# 6_ETHERCAT.net
KiCad netlist of a schematic drawn in Altium Designer
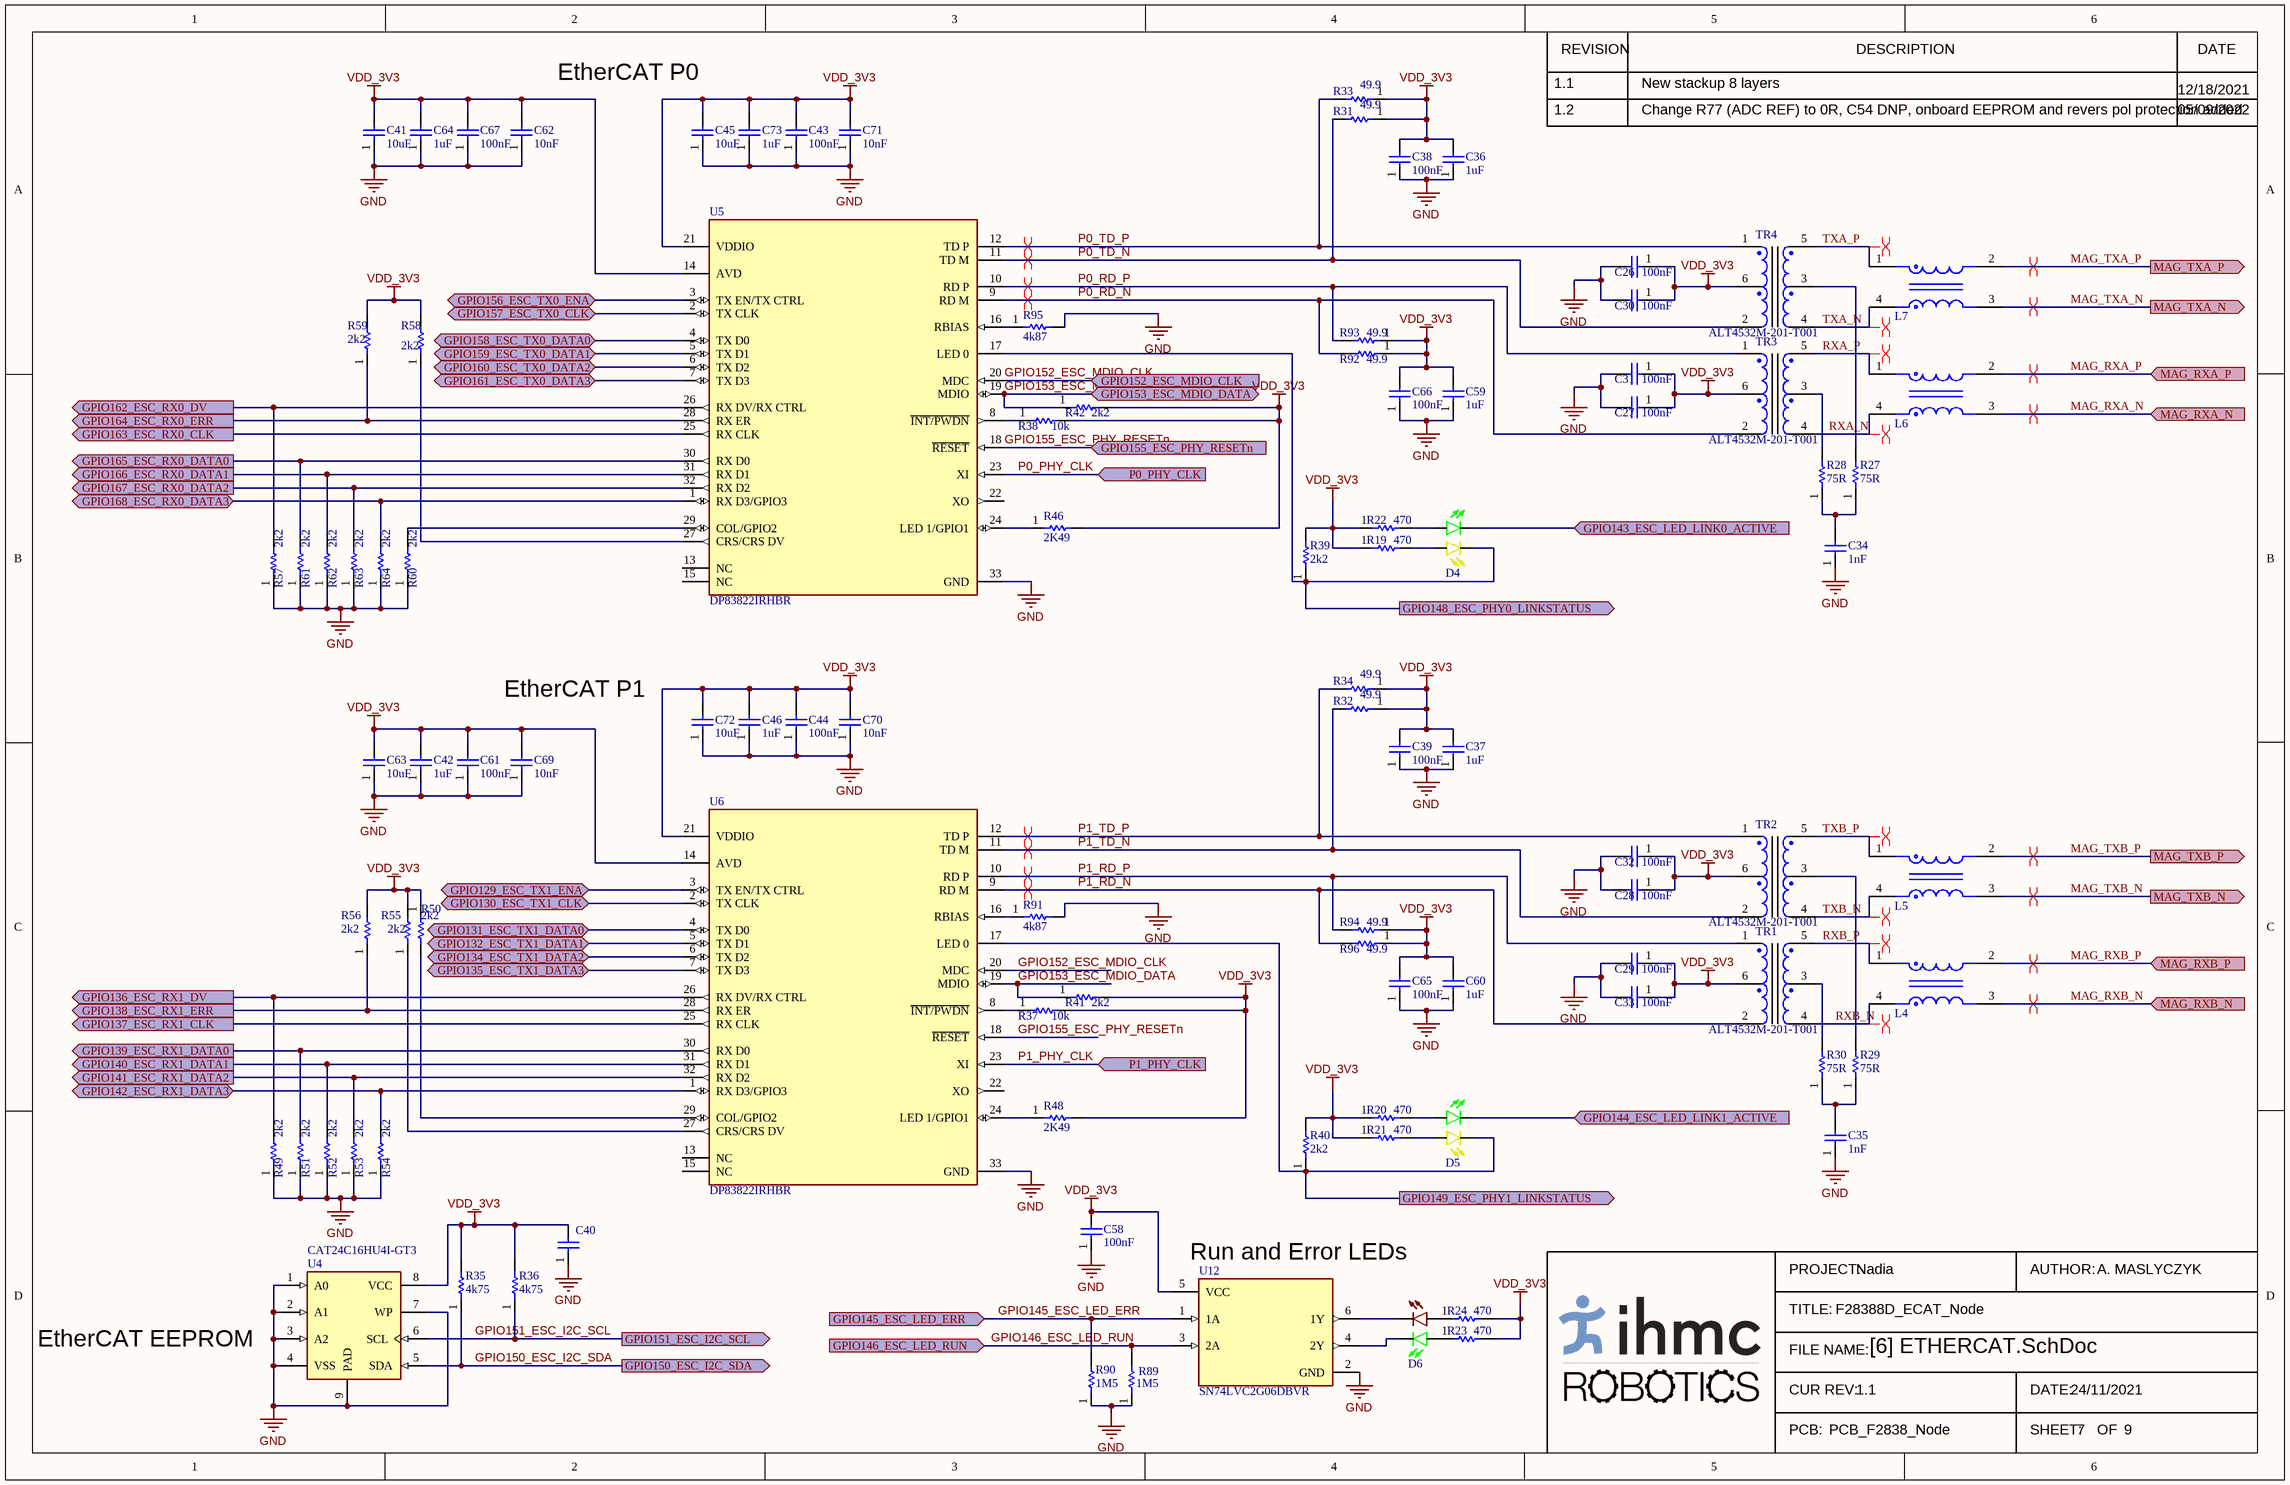
[diagram p0: [6] ETHERCAT.SchDoc]

(export (version "E")
  (design (tool "Eeschema 10.0.6"))
  (components
    (comp (ref "C26")
      (value "100nF")
      (footprint "CAPC1005X03N(0402)")
      (description "CAP CER 0.1UF 16V X7R 0402")
      (fields (field (name "MPN") "GRM155R71C104JA88D") (field (name "TOLERANCE") "5%"))
      (libsource (lib "IHMC_Altium_Lib") (part "100nF_16V_0402_CAP"))
    )
    (comp (ref "C27")
      (value "100nF")
      (footprint "CAPC1005X03N(0402)")
      (description "CAP CER 0.1UF 16V X7R 0402")
      (fields (field (name "MPN") "GRM155R71C104JA88D") (field (name "TOLERANCE") "5%"))
      (libsource (lib "IHMC_Altium_Lib") (part "100nF_16V_0402_CAP"))
    )
    (comp (ref "C28")
      (value "100nF")
      (footprint "CAPC1005X03N(0402)")
      (description "CAP CER 0.1UF 16V X7R 0402")
      (fields (field (name "MPN") "GRM155R71C104JA88D") (field (name "TOLERANCE") "5%"))
      (libsource (lib "IHMC_Altium_Lib") (part "100nF_16V_0402_CAP"))
    )
    (comp (ref "C29")
      (value "100nF")
      (footprint "CAPC1005X03N(0402)")
      (description "CAP CER 0.1UF 16V X7R 0402")
      (fields (field (name "MPN") "GRM155R71C104JA88D") (field (name "TOLERANCE") "5%"))
      (libsource (lib "IHMC_Altium_Lib") (part "100nF_16V_0402_CAP"))
    )
    (comp (ref "C30")
      (value "100nF")
      (footprint "CAPC1005X03N(0402)")
      (description "CAP CER 0.1UF 16V X7R 0402")
      (fields (field (name "MPN") "GRM155R71C104JA88D") (field (name "TOLERANCE") "5%"))
      (libsource (lib "IHMC_Altium_Lib") (part "100nF_16V_0402_CAP"))
    )
    (comp (ref "C31")
      (value "100nF")
      (footprint "CAPC1005X03N(0402)")
      (description "CAP CER 0.1UF 16V X7R 0402")
      (fields (field (name "MPN") "GRM155R71C104JA88D") (field (name "TOLERANCE") "5%"))
      (libsource (lib "IHMC_Altium_Lib") (part "100nF_16V_0402_CAP"))
    )
    (comp (ref "C32")
      (value "100nF")
      (footprint "CAPC1005X03N(0402)")
      (description "CAP CER 0.1UF 16V X7R 0402")
      (fields (field (name "MPN") "GRM155R71C104JA88D") (field (name "TOLERANCE") "5%"))
      (libsource (lib "IHMC_Altium_Lib") (part "100nF_16V_0402_CAP"))
    )
    (comp (ref "C33")
      (value "100nF")
      (footprint "CAPC1005X03N(0402)")
      (description "CAP CER 0.1UF 16V X7R 0402")
      (fields (field (name "MPN") "GRM155R71C104JA88D") (field (name "TOLERANCE") "5%"))
      (libsource (lib "IHMC_Altium_Lib") (part "100nF_16V_0402_CAP"))
    )
    (comp (ref "C34")
      (value "1nF")
      (footprint "0402_C")
      (description "CAP CER 1000PF 50V NP0 0402")
      (fields (field (name "TOLERANCE") "5%") (field (name "MANUFACTURER") "TDK"))
      (libsource (lib "IHMC_Altium_Lib") (part "1nF_50V_0402_C0G_CAP"))
    )
    (comp (ref "C35")
      (value "1nF")
      (footprint "0402_C")
      (description "CAP CER 1000PF 50V NP0 0402")
      (fields (field (name "TOLERANCE") "5%") (field (name "MANUFACTURER") "TDK"))
      (libsource (lib "IHMC_Altium_Lib") (part "1nF_50V_0402_C0G_CAP"))
    )
    (comp (ref "C36")
      (value "1uF")
      (footprint "CAPC1608X09N(0603)")
      (description "MLCC - SMD/SMT 25volts 1uF X5R 10%")
      (fields
        (field (name "MPN") "C0603C105K3PACTU")
        (field (name "VOLTAGE") "25VDC")
        (field (name "DRAWN BY") "TC")
      )
      (libsource (lib "IHMC_Altium_Lib") (part "1uF_25VDC_0603_Cap"))
    )
    (comp (ref "C37")
      (value "1uF")
      (footprint "CAPC1608X09N(0603)")
      (description "MLCC - SMD/SMT 25volts 1uF X5R 10%")
      (fields
        (field (name "MPN") "C0603C105K3PACTU")
        (field (name "VOLTAGE") "25VDC")
        (field (name "DRAWN BY") "TC")
      )
      (libsource (lib "IHMC_Altium_Lib") (part "1uF_25VDC_0603_Cap"))
    )
    (comp (ref "C38")
      (value "100nF")
      (footprint "CAPC1005X03N(0402)")
      (description "CAP CER 0.1UF 16V X7R 0402")
      (fields (field (name "MPN") "GRM155R71C104JA88D") (field (name "TOLERANCE") "5%"))
      (libsource (lib "IHMC_Altium_Lib") (part "100nF_16V_0402_CAP"))
    )
    (comp (ref "C39")
      (value "100nF")
      (footprint "CAPC1005X03N(0402)")
      (description "CAP CER 0.1UF 16V X7R 0402")
      (fields (field (name "MPN") "GRM155R71C104JA88D") (field (name "TOLERANCE") "5%"))
      (libsource (lib "IHMC_Altium_Lib") (part "100nF_16V_0402_CAP"))
    )
    (comp (ref "C40")
      (value "GRM155R71C104JA88D")
      (footprint "CAPC1005X03N(0402)")
      (description "CAP CER 0.1UF 16V X7R 0402")
      (fields (field (name "TOLERANCE") "5%"))
      (libsource (lib "IHMC_Altium_Lib") (part "100nF_16V_0402_CAP"))
    )
    (comp (ref "C41")
      (value "10uF")
      (footprint "CAPC1608X09N(0603)")
      (description "CAP CER 10UF 16V X6S 0603")
      (fields (field (name "MPN") "CL10X106MO8NRNC") (field (name "TOLERANCE") "20%"))
      (libsource (lib "IHMC_Altium_Lib") (part "10uF_16V_0603_CAP"))
    )
    (comp (ref "C42")
      (value "1uF")
      (footprint "CAPC1608X09N(0603)")
      (description "MLCC - SMD/SMT 25volts 1uF X5R 10%")
      (fields
        (field (name "MPN") "C0603C105K3PACTU")
        (field (name "VOLTAGE") "25VDC")
        (field (name "DRAWN BY") "TC")
      )
      (libsource (lib "IHMC_Altium_Lib") (part "1uF_25VDC_0603_Cap"))
    )
    (comp (ref "C43")
      (value "100nF")
      (footprint "CAPC1005X03N(0402)")
      (description "CAP CER 0.1UF 16V X7R 0402")
      (fields (field (name "MPN") "GRM155R71C104JA88D") (field (name "TOLERANCE") "5%"))
      (libsource (lib "IHMC_Altium_Lib") (part "100nF_16V_0402_CAP"))
    )
    (comp (ref "C44")
      (value "100nF")
      (footprint "CAPC1005X03N(0402)")
      (description "CAP CER 0.1UF 16V X7R 0402")
      (fields (field (name "MPN") "GRM155R71C104JA88D") (field (name "TOLERANCE") "5%"))
      (libsource (lib "IHMC_Altium_Lib") (part "100nF_16V_0402_CAP"))
    )
    (comp (ref "C45")
      (value "10uF")
      (footprint "CAPC1608X09N(0603)")
      (description "CAP CER 10UF 16V X6S 0603")
      (fields (field (name "MPN") "CL10X106MO8NRNC") (field (name "TOLERANCE") "20%"))
      (libsource (lib "IHMC_Altium_Lib") (part "10uF_16V_0603_CAP"))
    )
    (comp (ref "C46")
      (value "1uF")
      (footprint "CAPC1608X09N(0603)")
      (description "MLCC - SMD/SMT 25volts 1uF X5R 10%")
      (fields
        (field (name "MPN") "C0603C105K3PACTU")
        (field (name "VOLTAGE") "25VDC")
        (field (name "DRAWN BY") "TC")
      )
      (libsource (lib "IHMC_Altium_Lib") (part "1uF_25VDC_0603_Cap"))
    )
    (comp (ref "C58")
      (value "100nF")
      (footprint "CAPC1005X03N(0402)")
      (description "CAP CER 0.1UF 16V X7R 0402")
      (fields (field (name "MPN") "GRM155R71C104JA88D") (field (name "TOLERANCE") "5%"))
      (libsource (lib "IHMC_Altium_Lib") (part "100nF_16V_0402_CAP"))
    )
    (comp (ref "C59")
      (value "1uF")
      (footprint "CAPC1608X09N(0603)")
      (description "MLCC - SMD/SMT 25volts 1uF X5R 10%")
      (fields
        (field (name "MPN") "C0603C105K3PACTU")
        (field (name "VOLTAGE") "25VDC")
        (field (name "DRAWN BY") "TC")
      )
      (libsource (lib "IHMC_Altium_Lib") (part "1uF_25VDC_0603_Cap"))
    )
    (comp (ref "C60")
      (value "1uF")
      (footprint "CAPC1608X09N(0603)")
      (description "MLCC - SMD/SMT 25volts 1uF X5R 10%")
      (fields
        (field (name "MPN") "C0603C105K3PACTU")
        (field (name "VOLTAGE") "25VDC")
        (field (name "DRAWN BY") "TC")
      )
      (libsource (lib "IHMC_Altium_Lib") (part "1uF_25VDC_0603_Cap"))
    )
    (comp (ref "C61")
      (value "100nF")
      (footprint "CAPC1005X03N(0402)")
      (description "CAP CER 0.1UF 16V X7R 0402")
      (fields (field (name "MPN") "GRM155R71C104JA88D") (field (name "TOLERANCE") "5%"))
      (libsource (lib "IHMC_Altium_Lib") (part "100nF_16V_0402_CAP"))
    )
    (comp (ref "C62")
      (value "10nF")
      (footprint "CAPC1005X03N(0402)")
      (description "CAP CER 10000PF 50V X7R 0402")
      (fields (field (name "MPN") "CC0402KRX7R9BB103") (field (name "VOLTAGE") "50V"))
      (libsource (lib "IHMC_Altium_Lib") (part "10nF_50V_0402_CAP"))
    )
    (comp (ref "C63")
      (value "10uF")
      (footprint "CAPC1608X09N(0603)")
      (description "CAP CER 10UF 16V X6S 0603")
      (fields (field (name "MPN") "CL10X106MO8NRNC") (field (name "TOLERANCE") "20%"))
      (libsource (lib "IHMC_Altium_Lib") (part "10uF_16V_0603_CAP"))
    )
    (comp (ref "C64")
      (value "1uF")
      (footprint "CAPC1608X09N(0603)")
      (description "MLCC - SMD/SMT 25volts 1uF X5R 10%")
      (fields
        (field (name "MPN") "C0603C105K3PACTU")
        (field (name "VOLTAGE") "25VDC")
        (field (name "DRAWN BY") "TC")
      )
      (libsource (lib "IHMC_Altium_Lib") (part "1uF_25VDC_0603_Cap"))
    )
    (comp (ref "C65")
      (value "100nF")
      (footprint "CAPC1005X03N(0402)")
      (description "CAP CER 0.1UF 16V X7R 0402")
      (fields (field (name "MPN") "GRM155R71C104JA88D") (field (name "TOLERANCE") "5%"))
      (libsource (lib "IHMC_Altium_Lib") (part "100nF_16V_0402_CAP"))
    )
    (comp (ref "C66")
      (value "100nF")
      (footprint "CAPC1005X03N(0402)")
      (description "CAP CER 0.1UF 16V X7R 0402")
      (fields (field (name "MPN") "GRM155R71C104JA88D") (field (name "TOLERANCE") "5%"))
      (libsource (lib "IHMC_Altium_Lib") (part "100nF_16V_0402_CAP"))
    )
    (comp (ref "C67")
      (value "100nF")
      (footprint "CAPC1005X03N(0402)")
      (description "CAP CER 0.1UF 16V X7R 0402")
      (fields (field (name "MPN") "GRM155R71C104JA88D") (field (name "TOLERANCE") "5%"))
      (libsource (lib "IHMC_Altium_Lib") (part "100nF_16V_0402_CAP"))
    )
    (comp (ref "C69")
      (value "10nF")
      (footprint "CAPC1005X03N(0402)")
      (description "CAP CER 10000PF 50V X7R 0402")
      (fields (field (name "MPN") "CC0402KRX7R9BB103") (field (name "VOLTAGE") "50V"))
      (libsource (lib "IHMC_Altium_Lib") (part "10nF_50V_0402_CAP"))
    )
    (comp (ref "C70")
      (value "10nF")
      (footprint "CAPC1005X03N(0402)")
      (description "CAP CER 10000PF 50V X7R 0402")
      (fields (field (name "MPN") "CC0402KRX7R9BB103") (field (name "VOLTAGE") "50V"))
      (libsource (lib "IHMC_Altium_Lib") (part "10nF_50V_0402_CAP"))
    )
    (comp (ref "C71")
      (value "10nF")
      (footprint "CAPC1005X03N(0402)")
      (description "CAP CER 10000PF 50V X7R 0402")
      (fields (field (name "MPN") "CC0402KRX7R9BB103") (field (name "VOLTAGE") "50V"))
      (libsource (lib "IHMC_Altium_Lib") (part "10nF_50V_0402_CAP"))
    )
    (comp (ref "C72")
      (value "10uF")
      (footprint "CAPC1608X09N(0603)")
      (description "CAP CER 10UF 16V X6S 0603")
      (fields (field (name "MPN") "CL10X106MO8NRNC") (field (name "TOLERANCE") "20%"))
      (libsource (lib "IHMC_Altium_Lib") (part "10uF_16V_0603_CAP"))
    )
    (comp (ref "C73")
      (value "1uF")
      (footprint "CAPC1608X09N(0603)")
      (description "MLCC - SMD/SMT 25volts 1uF X5R 10%")
      (fields
        (field (name "MPN") "C0603C105K3PACTU")
        (field (name "VOLTAGE") "25VDC")
        (field (name "DRAWN BY") "TC")
      )
      (libsource (lib "IHMC_Altium_Lib") (part "1uF_25VDC_0603_Cap"))
    )
    (comp (ref "D4")
      (value "LTST-C195KGJSKT")
      (footprint "Dual_LED")
      (description "LED GREEN/YELLOW CLEAR CHIP SMD")
      (libsource (lib "IHMC_Altium_Lib") (part "Green/Yellow_LED"))
    )
    (comp (ref "D5")
      (value "LTST-C195KGJSKT")
      (footprint "Dual_LED")
      (description "LED GREEN/YELLOW CLEAR CHIP SMD")
      (libsource (lib "IHMC_Altium_Lib") (part "Green/Yellow_LED"))
    )
    (comp (ref "D6")
      (value "LTST-C195KGJRKT")
      (footprint "Dual_LED")
      (description "LED GREEN/RED CLEAR CHIP SMD")
      (libsource (lib "IHMC_Altium_Lib") (part "Green/Red_LED"))
    )
    (comp (ref "L4")
      (value "DLW21HN900SQ2L")
      (footprint "FP-DLW21HN-MFG")
      (fields (field (name "TOLERANCE") "25%") (field (name "MANUFACTURER") "Murata"))
      (libsource (lib "IHMC_Altium_Lib") (part "CM_CHOKE_90O_DLW21HN900SQ2L"))
    )
    (comp (ref "L5")
      (value "DLW21HN900SQ2L")
      (footprint "FP-DLW21HN-MFG")
      (fields (field (name "TOLERANCE") "25%") (field (name "MANUFACTURER") "Murata"))
      (libsource (lib "IHMC_Altium_Lib") (part "CM_CHOKE_90O_DLW21HN900SQ2L"))
    )
    (comp (ref "L6")
      (value "DLW21HN900SQ2L")
      (footprint "FP-DLW21HN-MFG")
      (fields (field (name "TOLERANCE") "25%") (field (name "MANUFACTURER") "Murata"))
      (libsource (lib "IHMC_Altium_Lib") (part "CM_CHOKE_90O_DLW21HN900SQ2L"))
    )
    (comp (ref "L7")
      (value "DLW21HN900SQ2L")
      (footprint "FP-DLW21HN-MFG")
      (fields (field (name "TOLERANCE") "25%") (field (name "MANUFACTURER") "Murata"))
      (libsource (lib "IHMC_Altium_Lib") (part "CM_CHOKE_90O_DLW21HN900SQ2L"))
    )
    (comp (ref "R19")
      (value "470")
      (footprint "0402")
      (description "Vishay CRCW Series Thick Film Resistor 0402 Case 470 5% 0.063W 200ppm/K")
      (fields
        (field (name "MANUFACTURER") "Vishay Dale")
        (field (name "MANUFACTURER PART NUMBER") "CRCW0402470RJNED")
      )
      (libsource (lib "IHMC_Altium_Lib") (part "470_1/10W_0402_CRCW0402470RJNED"))
    )
    (comp (ref "R20")
      (value "470")
      (footprint "0402")
      (description "Vishay CRCW Series Thick Film Resistor 0402 Case 470 5% 0.063W 200ppm/K")
      (fields
        (field (name "MANUFACTURER") "Vishay Dale")
        (field (name "MANUFACTURER PART NUMBER") "CRCW0402470RJNED")
      )
      (libsource (lib "IHMC_Altium_Lib") (part "470_1/10W_0402_CRCW0402470RJNED"))
    )
    (comp (ref "R21")
      (value "470")
      (footprint "0402")
      (description "Vishay CRCW Series Thick Film Resistor 0402 Case 470 5% 0.063W 200ppm/K")
      (fields
        (field (name "MANUFACTURER") "Vishay Dale")
        (field (name "MANUFACTURER PART NUMBER") "CRCW0402470RJNED")
      )
      (libsource (lib "IHMC_Altium_Lib") (part "470_1/10W_0402_CRCW0402470RJNED"))
    )
    (comp (ref "R22")
      (value "470")
      (footprint "0402")
      (description "Vishay CRCW Series Thick Film Resistor 0402 Case 470 5% 0.063W 200ppm/K")
      (fields
        (field (name "MANUFACTURER") "Vishay Dale")
        (field (name "MANUFACTURER PART NUMBER") "CRCW0402470RJNED")
      )
      (libsource (lib "IHMC_Altium_Lib") (part "470_1/10W_0402_CRCW0402470RJNED"))
    )
    (comp (ref "R23")
      (value "470")
      (footprint "0402")
      (description "Vishay CRCW Series Thick Film Resistor 0402 Case 470 5% 0.063W 200ppm/K")
      (fields
        (field (name "MANUFACTURER") "Vishay Dale")
        (field (name "MANUFACTURER PART NUMBER") "CRCW0402470RJNED")
      )
      (libsource (lib "IHMC_Altium_Lib") (part "470_1/10W_0402_CRCW0402470RJNED"))
    )
    (comp (ref "R24")
      (value "470")
      (footprint "0402")
      (description "Vishay CRCW Series Thick Film Resistor 0402 Case 470 5% 0.063W 200ppm/K")
      (fields
        (field (name "MANUFACTURER") "Vishay Dale")
        (field (name "MANUFACTURER PART NUMBER") "CRCW0402470RJNED")
      )
      (libsource (lib "IHMC_Altium_Lib") (part "470_1/10W_0402_CRCW0402470RJNED"))
    )
    (comp (ref "R27")
      (value "75R")
      (footprint "RESC1005X06N(0402)")
      (description "RES SMD 75 OHM 1% 1/16W 0402")
      (fields
        (field (name "MPN") "CRCW040275R0FKEDC")
        (field (name "TOLERANCE") "+/-1%")
        (field (name "DRAWN BY") "TC")
      )
      (libsource (lib "IHMC_Altium_Lib") (part "75R_1/10W_0402_RES"))
    )
    (comp (ref "R28")
      (value "75R")
      (footprint "RESC1005X06N(0402)")
      (description "RES SMD 75 OHM 1% 1/16W 0402")
      (fields
        (field (name "MPN") "CRCW040275R0FKEDC")
        (field (name "TOLERANCE") "+/-1%")
        (field (name "DRAWN BY") "TC")
      )
      (libsource (lib "IHMC_Altium_Lib") (part "75R_1/10W_0402_RES"))
    )
    (comp (ref "R29")
      (value "75R")
      (footprint "RESC1005X06N(0402)")
      (description "RES SMD 75 OHM 1% 1/16W 0402")
      (fields
        (field (name "MPN") "CRCW040275R0FKEDC")
        (field (name "TOLERANCE") "+/-1%")
        (field (name "DRAWN BY") "TC")
      )
      (libsource (lib "IHMC_Altium_Lib") (part "75R_1/10W_0402_RES"))
    )
    (comp (ref "R30")
      (value "75R")
      (footprint "RESC1005X06N(0402)")
      (description "RES SMD 75 OHM 1% 1/16W 0402")
      (fields
        (field (name "MPN") "CRCW040275R0FKEDC")
        (field (name "TOLERANCE") "+/-1%")
        (field (name "DRAWN BY") "TC")
      )
      (libsource (lib "IHMC_Altium_Lib") (part "75R_1/10W_0402_RES"))
    )
    (comp (ref "R31")
      (value "49.9")
      (footprint "RESC1005X06N(0402)")
      (description "RES SMD 49.9 OHM 1% 1/16W 0402")
      (fields
        (field (name "MPN") "CRCW040249R9FKED")
        (field (name "TOLERANCE") "1%")
        (field (name "DRAWN BY") "TC")
      )
      (libsource (lib "IHMC_Altium_Lib") (part "49R9_1/10W_0402_RES"))
    )
    (comp (ref "R32")
      (value "49.9")
      (footprint "RESC1005X06N(0402)")
      (description "RES SMD 49.9 OHM 1% 1/16W 0402")
      (fields
        (field (name "MPN") "CRCW040249R9FKED")
        (field (name "TOLERANCE") "1%")
        (field (name "DRAWN BY") "TC")
      )
      (libsource (lib "IHMC_Altium_Lib") (part "49R9_1/10W_0402_RES"))
    )
    (comp (ref "R33")
      (value "49.9")
      (footprint "RESC1005X06N(0402)")
      (description "RES SMD 49.9 OHM 1% 1/16W 0402")
      (fields
        (field (name "MPN") "CRCW040249R9FKED")
        (field (name "TOLERANCE") "1%")
        (field (name "DRAWN BY") "TC")
      )
      (libsource (lib "IHMC_Altium_Lib") (part "49R9_1/10W_0402_RES"))
    )
    (comp (ref "R34")
      (value "49.9")
      (footprint "RESC1005X06N(0402)")
      (description "RES SMD 49.9 OHM 1% 1/16W 0402")
      (fields
        (field (name "MPN") "CRCW040249R9FKED")
        (field (name "TOLERANCE") "1%")
        (field (name "DRAWN BY") "TC")
      )
      (libsource (lib "IHMC_Altium_Lib") (part "49R9_1/10W_0402_RES"))
    )
    (comp (ref "R35")
      (value "4k75")
      (footprint "RESC1005X06N(0402)")
      (description "RES SMD 4.75K OHM 1% 1/16W 0402")
      (fields (field (name "MPN") "RC0402FR-074K75L") (field (name "POWER") "1/16"))
      (libsource (lib "IHMC_Altium_Lib") (part "4k75_1/16_0402_RES"))
    )
    (comp (ref "R36")
      (value "4k75")
      (footprint "RESC1005X06N(0402)")
      (description "RES SMD 4.75K OHM 1% 1/16W 0402")
      (fields (field (name "MPN") "RC0402FR-074K75L") (field (name "POWER") "1/16"))
      (libsource (lib "IHMC_Altium_Lib") (part "4k75_1/16_0402_RES"))
    )
    (comp (ref "R37")
      (value "10k")
      (footprint "RESC1005X06N(0402)")
      (description "RES SMD 10K OHM 1% 1/16W 0402")
      (fields (field (name "TOLERANCE") "1%") (field (name "POWER") "1/16W"))
      (libsource (lib "IHMC_Altium_Lib") (part "10k_1/16W_0402_RES"))
    )
    (comp (ref "R38")
      (value "10k")
      (footprint "RESC1005X06N(0402)")
      (description "RES SMD 10K OHM 1% 1/16W 0402")
      (fields (field (name "TOLERANCE") "1%") (field (name "POWER") "1/16W"))
      (libsource (lib "IHMC_Altium_Lib") (part "10k_1/16W_0402_RES"))
    )
    (comp (ref "R39")
      (value "2k2")
      (footprint "0402")
      (description "Vishay CRCW Series Thick Film Resistor 0402 Case 2.2k 5% 0.063W 200ppm/K")
      (fields
        (field (name "MANUFACTURER") "Vishay Dale")
        (field (name "MANUFACTURER PART NUMBER") "CRCW04022K20JNED")
      )
      (libsource (lib "IHMC_Altium_Lib") (part "2k2_1/16_0402_CRCW04022K20JNED_RES"))
    )
    (comp (ref "R40")
      (value "2k2")
      (footprint "0402")
      (description "Vishay CRCW Series Thick Film Resistor 0402 Case 2.2k 5% 0.063W 200ppm/K")
      (fields
        (field (name "MANUFACTURER") "Vishay Dale")
        (field (name "MANUFACTURER PART NUMBER") "CRCW04022K20JNED")
      )
      (libsource (lib "IHMC_Altium_Lib") (part "2k2_1/16_0402_CRCW04022K20JNED_RES"))
    )
    (comp (ref "R41")
      (value "2k2")
      (footprint "0402")
      (description "Vishay CRCW Series Thick Film Resistor 0402 Case 2.2k 5% 0.063W 200ppm/K")
      (fields
        (field (name "MANUFACTURER") "Vishay Dale")
        (field (name "MANUFACTURER PART NUMBER") "CRCW04022K20JNED")
      )
      (libsource (lib "IHMC_Altium_Lib") (part "2k2_1/16_0402_CRCW04022K20JNED_RES"))
    )
    (comp (ref "R42")
      (value "2k2")
      (footprint "0402")
      (description "Vishay CRCW Series Thick Film Resistor 0402 Case 2.2k 5% 0.063W 200ppm/K")
      (fields
        (field (name "MANUFACTURER") "Vishay Dale")
        (field (name "MANUFACTURER PART NUMBER") "CRCW04022K20JNED")
      )
      (libsource (lib "IHMC_Altium_Lib") (part "2k2_1/16_0402_CRCW04022K20JNED_RES"))
    )
    (comp (ref "R46")
      (value "2K49")
      (footprint "0402")
      (fields
        (field (name "MANUFACTURER") "Vishay")
        (field (name "MANUFACTURER PART NUMBER") "CRCW04022K49FKED")
        (field (name "TOLERANCE") "1%")
      )
      (libsource (lib "IHMC_Altium_Lib") (part "2K49_1/16W_0402_CRCW04022K49FKED_RES"))
    )
    (comp (ref "R48")
      (value "2K49")
      (footprint "0402")
      (fields
        (field (name "MANUFACTURER") "Vishay")
        (field (name "MANUFACTURER PART NUMBER") "CRCW04022K49FKED")
        (field (name "TOLERANCE") "1%")
      )
      (libsource (lib "IHMC_Altium_Lib") (part "2K49_1/16W_0402_CRCW04022K49FKED_RES"))
    )
    (comp (ref "R49")
      (value "2k2")
      (footprint "0402")
      (description "Vishay CRCW Series Thick Film Resistor 0402 Case 2.2k 5% 0.063W 200ppm/K")
      (fields
        (field (name "MANUFACTURER") "Vishay Dale")
        (field (name "MANUFACTURER PART NUMBER") "CRCW04022K20JNED")
      )
      (libsource (lib "IHMC_Altium_Lib") (part "2k2_1/16_0402_CRCW04022K20JNED_RES"))
    )
    (comp (ref "R50")
      (value "2k2")
      (footprint "0402")
      (description "Vishay CRCW Series Thick Film Resistor 0402 Case 2.2k 5% 0.063W 200ppm/K")
      (fields
        (field (name "MANUFACTURER") "Vishay Dale")
        (field (name "MANUFACTURER PART NUMBER") "CRCW04022K20JNED")
      )
      (libsource (lib "IHMC_Altium_Lib") (part "2k2_1/16_0402_CRCW04022K20JNED_RES"))
    )
    (comp (ref "R51")
      (value "2k2")
      (footprint "0402")
      (description "Vishay CRCW Series Thick Film Resistor 0402 Case 2.2k 5% 0.063W 200ppm/K")
      (fields
        (field (name "MANUFACTURER") "Vishay Dale")
        (field (name "MANUFACTURER PART NUMBER") "CRCW04022K20JNED")
      )
      (libsource (lib "IHMC_Altium_Lib") (part "2k2_1/16_0402_CRCW04022K20JNED_RES"))
    )
    (comp (ref "R52")
      (value "2k2")
      (footprint "0402")
      (description "Vishay CRCW Series Thick Film Resistor 0402 Case 2.2k 5% 0.063W 200ppm/K")
      (fields
        (field (name "MANUFACTURER") "Vishay Dale")
        (field (name "MANUFACTURER PART NUMBER") "CRCW04022K20JNED")
      )
      (libsource (lib "IHMC_Altium_Lib") (part "2k2_1/16_0402_CRCW04022K20JNED_RES"))
    )
    (comp (ref "R53")
      (value "2k2")
      (footprint "0402")
      (description "Vishay CRCW Series Thick Film Resistor 0402 Case 2.2k 5% 0.063W 200ppm/K")
      (fields
        (field (name "MANUFACTURER") "Vishay Dale")
        (field (name "MANUFACTURER PART NUMBER") "CRCW04022K20JNED")
      )
      (libsource (lib "IHMC_Altium_Lib") (part "2k2_1/16_0402_CRCW04022K20JNED_RES"))
    )
    (comp (ref "R54")
      (value "2k2")
      (footprint "0402")
      (description "Vishay CRCW Series Thick Film Resistor 0402 Case 2.2k 5% 0.063W 200ppm/K")
      (fields
        (field (name "MANUFACTURER") "Vishay Dale")
        (field (name "MANUFACTURER PART NUMBER") "CRCW04022K20JNED")
      )
      (libsource (lib "IHMC_Altium_Lib") (part "2k2_1/16_0402_CRCW04022K20JNED_RES"))
    )
    (comp (ref "R55")
      (value "2k2")
      (footprint "0402")
      (description "Vishay CRCW Series Thick Film Resistor 0402 Case 2.2k 5% 0.063W 200ppm/K")
      (fields
        (field (name "MANUFACTURER") "Vishay Dale")
        (field (name "MANUFACTURER PART NUMBER") "CRCW04022K20JNED")
      )
      (libsource (lib "IHMC_Altium_Lib") (part "2k2_1/16_0402_CRCW04022K20JNED_RES"))
    )
    (comp (ref "R56")
      (value "2k2")
      (footprint "0402")
      (description "Vishay CRCW Series Thick Film Resistor 0402 Case 2.2k 5% 0.063W 200ppm/K")
      (fields
        (field (name "MANUFACTURER") "Vishay Dale")
        (field (name "MANUFACTURER PART NUMBER") "CRCW04022K20JNED")
      )
      (libsource (lib "IHMC_Altium_Lib") (part "2k2_1/16_0402_CRCW04022K20JNED_RES"))
    )
    (comp (ref "R57")
      (value "2k2")
      (footprint "0402")
      (description "Vishay CRCW Series Thick Film Resistor 0402 Case 2.2k 5% 0.063W 200ppm/K")
      (fields
        (field (name "MANUFACTURER") "Vishay Dale")
        (field (name "MANUFACTURER PART NUMBER") "CRCW04022K20JNED")
      )
      (libsource (lib "IHMC_Altium_Lib") (part "2k2_1/16_0402_CRCW04022K20JNED_RES"))
    )
    (comp (ref "R58")
      (value "2k2")
      (footprint "0402")
      (description "Vishay CRCW Series Thick Film Resistor 0402 Case 2.2k 5% 0.063W 200ppm/K")
      (fields
        (field (name "MANUFACTURER") "Vishay Dale")
        (field (name "MANUFACTURER PART NUMBER") "CRCW04022K20JNED")
      )
      (libsource (lib "IHMC_Altium_Lib") (part "2k2_1/16_0402_CRCW04022K20JNED_RES"))
    )
    (comp (ref "R59")
      (value "2k2")
      (footprint "0402")
      (description "Vishay CRCW Series Thick Film Resistor 0402 Case 2.2k 5% 0.063W 200ppm/K")
      (fields
        (field (name "MANUFACTURER") "Vishay Dale")
        (field (name "MANUFACTURER PART NUMBER") "CRCW04022K20JNED")
      )
      (libsource (lib "IHMC_Altium_Lib") (part "2k2_1/16_0402_CRCW04022K20JNED_RES"))
    )
    (comp (ref "R60")
      (value "2k2")
      (footprint "0402")
      (description "Vishay CRCW Series Thick Film Resistor 0402 Case 2.2k 5% 0.063W 200ppm/K")
      (fields
        (field (name "MANUFACTURER") "Vishay Dale")
        (field (name "MANUFACTURER PART NUMBER") "CRCW04022K20JNED")
      )
      (libsource (lib "IHMC_Altium_Lib") (part "2k2_1/16_0402_CRCW04022K20JNED_RES"))
    )
    (comp (ref "R61")
      (value "2k2")
      (footprint "0402")
      (description "Vishay CRCW Series Thick Film Resistor 0402 Case 2.2k 5% 0.063W 200ppm/K")
      (fields
        (field (name "MANUFACTURER") "Vishay Dale")
        (field (name "MANUFACTURER PART NUMBER") "CRCW04022K20JNED")
      )
      (libsource (lib "IHMC_Altium_Lib") (part "2k2_1/16_0402_CRCW04022K20JNED_RES"))
    )
    (comp (ref "R62")
      (value "2k2")
      (footprint "0402")
      (description "Vishay CRCW Series Thick Film Resistor 0402 Case 2.2k 5% 0.063W 200ppm/K")
      (fields
        (field (name "MANUFACTURER") "Vishay Dale")
        (field (name "MANUFACTURER PART NUMBER") "CRCW04022K20JNED")
      )
      (libsource (lib "IHMC_Altium_Lib") (part "2k2_1/16_0402_CRCW04022K20JNED_RES"))
    )
    (comp (ref "R63")
      (value "2k2")
      (footprint "0402")
      (description "Vishay CRCW Series Thick Film Resistor 0402 Case 2.2k 5% 0.063W 200ppm/K")
      (fields
        (field (name "MANUFACTURER") "Vishay Dale")
        (field (name "MANUFACTURER PART NUMBER") "CRCW04022K20JNED")
      )
      (libsource (lib "IHMC_Altium_Lib") (part "2k2_1/16_0402_CRCW04022K20JNED_RES"))
    )
    (comp (ref "R64")
      (value "2k2")
      (footprint "0402")
      (description "Vishay CRCW Series Thick Film Resistor 0402 Case 2.2k 5% 0.063W 200ppm/K")
      (fields
        (field (name "MANUFACTURER") "Vishay Dale")
        (field (name "MANUFACTURER PART NUMBER") "CRCW04022K20JNED")
      )
      (libsource (lib "IHMC_Altium_Lib") (part "2k2_1/16_0402_CRCW04022K20JNED_RES"))
    )
    (comp (ref "R89")
      (value "1M5")
      (footprint "0402")
      (description "RES SMD 1.5M OHM 5% 1/16W 0402")
      (fields
        (field (name "MANUFACTURER") "Vishay Dale")
        (field (name "MANUFACTURER PART NUMBER") "CRCW04021M50JNED")
      )
      (libsource (lib "IHMC_Altium_Lib") (part "1M5_1/16W_0402_CRCW04021M50JNED_RES"))
    )
    (comp (ref "R90")
      (value "1M5")
      (footprint "0402")
      (description "RES SMD 1.5M OHM 5% 1/16W 0402")
      (fields
        (field (name "MANUFACTURER") "Vishay Dale")
        (field (name "MANUFACTURER PART NUMBER") "CRCW04021M50JNED")
      )
      (libsource (lib "IHMC_Altium_Lib") (part "1M5_1/16W_0402_CRCW04021M50JNED_RES"))
    )
    (comp (ref "R91")
      (value "4k87")
      (footprint "0402")
      (description "Res Thick Film 0402 4.87K Ohm 1% 1/16W 100ppm/C Molded SMD SMD Paper T/R")
      (fields
        (field (name "MANUFACTURER") "Vishay")
        (field (name "MANUFACTURER PART NUMBER") "CRCW04024K87FKED")
      )
      (libsource (lib "IHMC_Altium_Lib") (part "4K87_0402_1/16W_CRCW04024K87FKED_RES"))
    )
    (comp (ref "R92")
      (value "49.9")
      (footprint "RESC1005X06N(0402)")
      (description "RES SMD 49.9 OHM 1% 1/16W 0402")
      (fields
        (field (name "MPN") "CRCW040249R9FKED")
        (field (name "TOLERANCE") "1%")
        (field (name "DRAWN BY") "TC")
      )
      (libsource (lib "IHMC_Altium_Lib") (part "49R9_1/10W_0402_RES"))
    )
    (comp (ref "R93")
      (value "49.9")
      (footprint "RESC1005X06N(0402)")
      (description "RES SMD 49.9 OHM 1% 1/16W 0402")
      (fields
        (field (name "MPN") "CRCW040249R9FKED")
        (field (name "TOLERANCE") "1%")
        (field (name "DRAWN BY") "TC")
      )
      (libsource (lib "IHMC_Altium_Lib") (part "49R9_1/10W_0402_RES"))
    )
    (comp (ref "R94")
      (value "49.9")
      (footprint "RESC1005X06N(0402)")
      (description "RES SMD 49.9 OHM 1% 1/16W 0402")
      (fields
        (field (name "MPN") "CRCW040249R9FKED")
        (field (name "TOLERANCE") "1%")
        (field (name "DRAWN BY") "TC")
      )
      (libsource (lib "IHMC_Altium_Lib") (part "49R9_1/10W_0402_RES"))
    )
    (comp (ref "R95")
      (value "4k87")
      (footprint "0402")
      (description "Res Thick Film 0402 4.87K Ohm 1% 1/16W 100ppm/C Molded SMD SMD Paper T/R")
      (fields
        (field (name "MANUFACTURER") "Vishay")
        (field (name "MANUFACTURER PART NUMBER") "CRCW04024K87FKED")
      )
      (libsource (lib "IHMC_Altium_Lib") (part "4K87_0402_1/16W_CRCW04024K87FKED_RES"))
    )
    (comp (ref "R96")
      (value "49.9")
      (footprint "RESC1005X06N(0402)")
      (description "RES SMD 49.9 OHM 1% 1/16W 0402")
      (fields
        (field (name "MPN") "CRCW040249R9FKED")
        (field (name "TOLERANCE") "1%")
        (field (name "DRAWN BY") "TC")
      )
      (libsource (lib "IHMC_Altium_Lib") (part "49R9_1/10W_0402_RES"))
    )
    (comp (ref "TR1")
      (value "ALT4532M-201-T001")
      (footprint "ALT4532M_LAN_Transformer")
      (description "Telecom Transformer 1CT:1CT 6 Terminal SMD")
      (fields (field (name "MANUFACTURER") "TDK"))
      (libsource (lib "IHMC_Altium_Lib") (part "Pulse_Transfo_LAN_ALT4532M-201-T001"))
    )
    (comp (ref "TR2")
      (value "ALT4532M-201-T001")
      (footprint "ALT4532M_LAN_Transformer")
      (description "Telecom Transformer 1CT:1CT 6 Terminal SMD")
      (fields (field (name "MANUFACTURER") "TDK"))
      (libsource (lib "IHMC_Altium_Lib") (part "Pulse_Transfo_LAN_ALT4532M-201-T001"))
    )
    (comp (ref "TR3")
      (value "ALT4532M-201-T001")
      (footprint "ALT4532M_LAN_Transformer")
      (description "Telecom Transformer 1CT:1CT 6 Terminal SMD")
      (fields (field (name "MANUFACTURER") "TDK"))
      (libsource (lib "IHMC_Altium_Lib") (part "Pulse_Transfo_LAN_ALT4532M-201-T001"))
    )
    (comp (ref "TR4")
      (value "ALT4532M-201-T001")
      (footprint "ALT4532M_LAN_Transformer")
      (description "Telecom Transformer 1CT:1CT 6 Terminal SMD")
      (fields (field (name "MANUFACTURER") "TDK"))
      (libsource (lib "IHMC_Altium_Lib") (part "Pulse_Transfo_LAN_ALT4532M-201-T001"))
    )
    (comp (ref "U4")
      (value "CAT24C16HU4I-GT3")
      (footprint "UDFN8-EP")
      (description "EEPROM Serial-2Wire 16K-bit 2K x 8 1.8V/2.5V/3.3V/5V Automotive 8-Pin UDFN EP T/R")
      (fields (field (name "MANUFACTURER") "ON Semiconductor"))
      (libsource (lib "IHMC_Altium_Lib") (part "CAT24C16HU4I-GT3_EEPROM_16Kb"))
    )
    (comp (ref "U5")
      (value "DP83822IRHBR")
      (footprint "FP-RHB0032B-MFG")
      (description "IC TXRX ETHERNET 32VQFN")
      (fields (field (name "MANUFACTURER") "Texas Instruments"))
      (libsource (lib "IHMC_Altium_Lib") (part "PHY_ETHER_ DP83822IRHBR"))
    )
    (comp (ref "U6")
      (value "DP83822IRHBR")
      (footprint "FP-RHB0032B-MFG")
      (description "IC TXRX ETHERNET 32VQFN")
      (fields (field (name "MANUFACTURER") "Texas Instruments"))
      (libsource (lib "IHMC_Altium_Lib") (part "PHY_ETHER_ DP83822IRHBR"))
    )
    (comp (ref "U12")
      (value "SN74LVC2G06DBVR")
      (footprint "FP-DBV0006A-IPC_C")
      (description "Buffer/Driver 2-CH Inverting Open Drain CMOS 6-Pin SOT-23 T/R")
      (fields (field (name "MANUFACTURER") "Texas Instruments"))
      (libsource (lib "IHMC_Altium_Lib") (part "BUF_dual_SN74LVC2G06DBVR"))
    )
  )
  (nets
    (net (code "1") (name "/GPIO129_ESC_TX1_ENA") (class "Default")
      (node (ref "U6") (pin "3") (pinfunction "TX_EN/TX_CTRL_3") (pintype "bidirectional"))
    )
    (net (code "2") (name "/GPIO130_ESC_TX1_CLK") (class "Default")
      (node (ref "U6") (pin "2") (pinfunction "TX_CLK_2") (pintype "bidirectional"))
    )
    (net (code "3") (name "/GPIO131_ESC_TX1_DATA0") (class "Default")
      (node (ref "U6") (pin "4") (pinfunction "TX_D0_4") (pintype "bidirectional"))
    )
    (net (code "4") (name "/GPIO132_ESC_TX1_DATA1") (class "Default")
      (node (ref "U6") (pin "5") (pinfunction "TX_D1_5") (pintype "bidirectional"))
    )
    (net (code "5") (name "/GPIO134_ESC_TX1_DATA2") (class "Default")
      (node (ref "U6") (pin "6") (pinfunction "TX_D2_6") (pintype "bidirectional"))
    )
    (net (code "6") (name "/GPIO135_ESC_TX1_DATA3") (class "Default")
      (node (ref "U6") (pin "7") (pinfunction "TX_D3_7") (pintype "bidirectional"))
    )
    (net (code "7") (name "/GPIO136_ESC_RX1_DV") (class "Default")
      (node (ref "R49") (pin "2") (pinfunction "2_2") (pintype "passive"))
      (node (ref "U6") (pin "26") (pinfunction "RX_DV/RX_CTRL_26") (pintype "output"))
    )
    (net (code "8") (name "/GPIO137_ESC_RX1_CLK") (class "Default")
      (node (ref "U6") (pin "25") (pinfunction "RX_CLK_25") (pintype "output"))
    )
    (net (code "9") (name "/GPIO138_ESC_RX1_ERR") (class "Default")
      (node (ref "R56") (pin "1") (pinfunction "1_1") (pintype "passive"))
      (node (ref "U6") (pin "28") (pinfunction "RX_ER_28") (pintype "output"))
    )
    (net (code "10") (name "/GPIO139_ESC_RX1_DATA0") (class "Default")
      (node (ref "R51") (pin "2") (pinfunction "2_2") (pintype "passive"))
      (node (ref "U6") (pin "30") (pinfunction "RX_D0_30") (pintype "output"))
    )
    (net (code "11") (name "/GPIO140_ESC_RX1_DATA1") (class "Default")
      (node (ref "R52") (pin "2") (pinfunction "2_2") (pintype "passive"))
      (node (ref "U6") (pin "31") (pinfunction "RX_D1_31") (pintype "output"))
    )
    (net (code "12") (name "/GPIO141_ESC_RX1_DATA2") (class "Default")
      (node (ref "R53") (pin "2") (pinfunction "2_2") (pintype "passive"))
      (node (ref "U6") (pin "32") (pinfunction "RX_D2_32") (pintype "output"))
    )
    (net (code "13") (name "/GPIO142_ESC_RX1_DATA3") (class "Default")
      (node (ref "R54") (pin "2") (pinfunction "2_2") (pintype "passive"))
      (node (ref "U6") (pin "1") (pinfunction "RX_D3/GPIO3_1") (pintype "bidirectional"))
    )
    (net (code "14") (name "/GPIO143_ESC_LED_LINK0_ACTIVE") (class "Default")
      (node (ref "D4") (pin "3") (pinfunction "3_3") (pintype "passive"))
    )
    (net (code "15") (name "/GPIO144_ESC_LED_LINK1_ACTIVE") (class "Default")
      (node (ref "D5") (pin "3") (pinfunction "3_3") (pintype "passive"))
    )
    (net (code "16") (name "/GPIO145_ESC_LED_ERR") (class "Default")
      (node (ref "R90") (pin "2") (pinfunction "2_2") (pintype "passive"))
      (node (ref "U12") (pin "1") (pinfunction "1A_1") (pintype "input"))
    )
    (net (code "17") (name "/GPIO146_ESC_LED_RUN") (class "Default")
      (node (ref "R89") (pin "2") (pinfunction "2_2") (pintype "passive"))
      (node (ref "U12") (pin "3") (pinfunction "2A_3") (pintype "input"))
    )
    (net (code "18") (name "/GPIO148_ESC_PHY0_LINKSTATUS") (class "Default")
      (node (ref "D4") (pin "4") (pinfunction "4_4") (pintype "passive"))
      (node (ref "R39") (pin "1") (pinfunction "1_1") (pintype "passive"))
      (node (ref "U5") (pin "17") (pinfunction "LED_0_17") (pintype "passive"))
    )
    (net (code "19") (name "/GPIO149_ESC_PHY1_LINKSTATUS") (class "Default")
      (node (ref "D5") (pin "4") (pinfunction "4_4") (pintype "passive"))
      (node (ref "R40") (pin "1") (pinfunction "1_1") (pintype "passive"))
      (node (ref "U6") (pin "17") (pinfunction "LED_0_17") (pintype "passive"))
    )
    (net (code "20") (name "/GPIO150_ESC_I2C_SDA") (class "Default")
      (node (ref "R35") (pin "1") (pinfunction "1_1") (pintype "passive"))
      (node (ref "U4") (pin "5") (pinfunction "SDA_5") (pintype "input"))
    )
    (net (code "21") (name "/GPIO151_ESC_I2C_SCL") (class "Default")
      (node (ref "R36") (pin "1") (pinfunction "1_1") (pintype "passive"))
      (node (ref "U4") (pin "6") (pinfunction "SCL_6") (pintype "input"))
    )
    (net (code "22") (name "/GPIO152_ESC_MDIO_CLK") (class "Default")
      (node (ref "U5") (pin "20") (pinfunction "MDC_20") (pintype "input"))
      (node (ref "U6") (pin "20") (pinfunction "MDC_20") (pintype "input"))
    )
    (net (code "23") (name "/GPIO153_ESC_MDIO_DATA") (class "Default")
      (node (ref "R41") (pin "1") (pinfunction "1_1") (pintype "passive"))
      (node (ref "R42") (pin "1") (pinfunction "1_1") (pintype "passive"))
      (node (ref "U5") (pin "19") (pinfunction "MDIO_19") (pintype "bidirectional"))
      (node (ref "U6") (pin "19") (pinfunction "MDIO_19") (pintype "bidirectional"))
    )
    (net (code "24") (name "/GPIO155_ESC_PHY_RESETn") (class "Default")
      (node (ref "U5") (pin "18") (pinfunction "~{RESET}_18") (pintype "input"))
      (node (ref "U6") (pin "18") (pinfunction "~{RESET}_18") (pintype "input"))
    )
    (net (code "25") (name "/GPIO156_ESC_TX0_ENA") (class "Default")
      (node (ref "U5") (pin "3") (pinfunction "TX_EN/TX_CTRL_3") (pintype "bidirectional"))
    )
    (net (code "26") (name "/GPIO157_ESC_TX0_CLK") (class "Default")
      (node (ref "U5") (pin "2") (pinfunction "TX_CLK_2") (pintype "bidirectional"))
    )
    (net (code "27") (name "/GPIO158_ESC_TX0_DATA0") (class "Default")
      (node (ref "U5") (pin "4") (pinfunction "TX_D0_4") (pintype "bidirectional"))
    )
    (net (code "28") (name "/GPIO159_ESC_TX0_DATA1") (class "Default")
      (node (ref "U5") (pin "5") (pinfunction "TX_D1_5") (pintype "bidirectional"))
    )
    (net (code "29") (name "/GPIO160_ESC_TX0_DATA2") (class "Default")
      (node (ref "U5") (pin "6") (pinfunction "TX_D2_6") (pintype "bidirectional"))
    )
    (net (code "30") (name "/GPIO161_ESC_TX0_DATA3") (class "Default")
      (node (ref "U5") (pin "7") (pinfunction "TX_D3_7") (pintype "bidirectional"))
    )
    (net (code "31") (name "/GPIO162_ESC_RX0_DV") (class "Default")
      (node (ref "R57") (pin "2") (pinfunction "2_2") (pintype "passive"))
      (node (ref "U5") (pin "26") (pinfunction "RX_DV/RX_CTRL_26") (pintype "output"))
    )
    (net (code "32") (name "/GPIO163_ESC_RX0_CLK") (class "Default")
      (node (ref "U5") (pin "25") (pinfunction "RX_CLK_25") (pintype "output"))
    )
    (net (code "33") (name "/GPIO164_ESC_RX0_ERR") (class "Default")
      (node (ref "R59") (pin "1") (pinfunction "1_1") (pintype "passive"))
      (node (ref "U5") (pin "28") (pinfunction "RX_ER_28") (pintype "output"))
    )
    (net (code "34") (name "/GPIO165_ESC_RX0_DATA0") (class "Default")
      (node (ref "R61") (pin "2") (pinfunction "2_2") (pintype "passive"))
      (node (ref "U5") (pin "30") (pinfunction "RX_D0_30") (pintype "output"))
    )
    (net (code "35") (name "/GPIO166_ESC_RX0_DATA1") (class "Default")
      (node (ref "R62") (pin "2") (pinfunction "2_2") (pintype "passive"))
      (node (ref "U5") (pin "31") (pinfunction "RX_D1_31") (pintype "output"))
    )
    (net (code "36") (name "/GPIO167_ESC_RX0_DATA2") (class "Default")
      (node (ref "R63") (pin "2") (pinfunction "2_2") (pintype "passive"))
      (node (ref "U5") (pin "32") (pinfunction "RX_D2_32") (pintype "output"))
    )
    (net (code "37") (name "/GPIO168_ESC_RX0_DATA3") (class "Default")
      (node (ref "R64") (pin "2") (pinfunction "2_2") (pintype "passive"))
      (node (ref "U5") (pin "1") (pinfunction "RX_D3/GPIO3_1") (pintype "bidirectional"))
    )
    (net (code "38") (name "/MAG_RXA_N") (class "Default")
      (node (ref "L6") (pin "3") (pinfunction "3_3") (pintype "passive"))
    )
    (net (code "39") (name "/MAG_RXA_P") (class "Default")
      (node (ref "L6") (pin "2") (pinfunction "2_2") (pintype "passive"))
    )
    (net (code "40") (name "/MAG_RXB_N") (class "Default")
      (node (ref "L4") (pin "3") (pinfunction "3_3") (pintype "passive"))
    )
    (net (code "41") (name "/MAG_RXB_P") (class "Default")
      (node (ref "L4") (pin "2") (pinfunction "2_2") (pintype "passive"))
    )
    (net (code "42") (name "/MAG_TXA_N") (class "Default")
      (node (ref "L7") (pin "3") (pinfunction "3_3") (pintype "passive"))
    )
    (net (code "43") (name "/MAG_TXA_P") (class "Default")
      (node (ref "L7") (pin "2") (pinfunction "2_2") (pintype "passive"))
    )
    (net (code "44") (name "/MAG_TXB_N") (class "Default")
      (node (ref "L5") (pin "3") (pinfunction "3_3") (pintype "passive"))
    )
    (net (code "45") (name "/MAG_TXB_P") (class "Default")
      (node (ref "L5") (pin "2") (pinfunction "2_2") (pintype "passive"))
    )
    (net (code "46") (name "/P0_PHY_CLK") (class "Default")
      (node (ref "U5") (pin "23") (pinfunction "XI_23") (pintype "input"))
    )
    (net (code "47") (name "/P0_RD_N") (class "Default")
      (node (ref "R92") (pin "2") (pinfunction "2_2") (pintype "passive"))
      (node (ref "TR3") (pin "2") (pinfunction "2_2") (pintype "passive"))
      (node (ref "U5") (pin "9") (pinfunction "RD_M_9") (pintype "passive"))
    )
    (net (code "48") (name "/P0_RD_P") (class "Default")
      (node (ref "R93") (pin "2") (pinfunction "2_2") (pintype "passive"))
      (node (ref "TR3") (pin "1") (pinfunction "1_1") (pintype "passive"))
      (node (ref "U5") (pin "10") (pinfunction "RD_P_10") (pintype "passive"))
    )
    (net (code "49") (name "/P0_TD_N") (class "Default")
      (node (ref "R31") (pin "2") (pinfunction "2_2") (pintype "passive"))
      (node (ref "TR4") (pin "2") (pinfunction "2_2") (pintype "passive"))
      (node (ref "U5") (pin "11") (pinfunction "TD_M_11") (pintype "passive"))
    )
    (net (code "50") (name "/P0_TD_P") (class "Default")
      (node (ref "R33") (pin "2") (pinfunction "2_2") (pintype "passive"))
      (node (ref "TR4") (pin "1") (pinfunction "1_1") (pintype "passive"))
      (node (ref "U5") (pin "12") (pinfunction "TD_P_12") (pintype "passive"))
    )
    (net (code "51") (name "/P1_PHY_CLK") (class "Default")
      (node (ref "U6") (pin "23") (pinfunction "XI_23") (pintype "input"))
    )
    (net (code "52") (name "/P1_RD_N") (class "Default")
      (node (ref "R96") (pin "2") (pinfunction "2_2") (pintype "passive"))
      (node (ref "TR1") (pin "2") (pinfunction "2_2") (pintype "passive"))
      (node (ref "U6") (pin "9") (pinfunction "RD_M_9") (pintype "passive"))
    )
    (net (code "53") (name "/P1_RD_P") (class "Default")
      (node (ref "R94") (pin "2") (pinfunction "2_2") (pintype "passive"))
      (node (ref "TR1") (pin "1") (pinfunction "1_1") (pintype "passive"))
      (node (ref "U6") (pin "10") (pinfunction "RD_P_10") (pintype "passive"))
    )
    (net (code "54") (name "/P1_TD_N") (class "Default")
      (node (ref "R32") (pin "2") (pinfunction "2_2") (pintype "passive"))
      (node (ref "TR2") (pin "2") (pinfunction "2_2") (pintype "passive"))
      (node (ref "U6") (pin "11") (pinfunction "TD_M_11") (pintype "passive"))
    )
    (net (code "55") (name "/P1_TD_P") (class "Default")
      (node (ref "R34") (pin "2") (pinfunction "2_2") (pintype "passive"))
      (node (ref "TR2") (pin "1") (pinfunction "1_1") (pintype "passive"))
      (node (ref "U6") (pin "12") (pinfunction "TD_P_12") (pintype "passive"))
    )
    (net (code "56") (name "/RXA_N") (class "Default")
      (node (ref "L6") (pin "4") (pinfunction "4_4") (pintype "passive"))
      (node (ref "TR3") (pin "4") (pinfunction "4_4") (pintype "passive"))
    )
    (net (code "57") (name "/RXA_P") (class "Default")
      (node (ref "L6") (pin "1") (pinfunction "1_1") (pintype "passive"))
      (node (ref "TR3") (pin "5") (pinfunction "5_5") (pintype "passive"))
    )
    (net (code "58") (name "/RXB_N") (class "Default")
      (node (ref "L4") (pin "4") (pinfunction "4_4") (pintype "passive"))
      (node (ref "TR1") (pin "4") (pinfunction "4_4") (pintype "passive"))
    )
    (net (code "59") (name "/RXB_P") (class "Default")
      (node (ref "L4") (pin "1") (pinfunction "1_1") (pintype "passive"))
      (node (ref "TR1") (pin "5") (pinfunction "5_5") (pintype "passive"))
    )
    (net (code "60") (name "/TXA_N") (class "Default")
      (node (ref "L7") (pin "4") (pinfunction "4_4") (pintype "passive"))
      (node (ref "TR4") (pin "4") (pinfunction "4_4") (pintype "passive"))
    )
    (net (code "61") (name "/TXA_P") (class "Default")
      (node (ref "L7") (pin "1") (pinfunction "1_1") (pintype "passive"))
      (node (ref "TR4") (pin "5") (pinfunction "5_5") (pintype "passive"))
    )
    (net (code "62") (name "/TXB_N") (class "Default")
      (node (ref "L5") (pin "4") (pinfunction "4_4") (pintype "passive"))
      (node (ref "TR2") (pin "4") (pinfunction "4_4") (pintype "passive"))
    )
    (net (code "63") (name "/TXB_P") (class "Default")
      (node (ref "L5") (pin "1") (pinfunction "1_1") (pintype "passive"))
      (node (ref "TR2") (pin "5") (pinfunction "5_5") (pintype "passive"))
    )
    (net (code "64") (name "GND") (class "Default")
      (node (ref "C26") (pin "2") (pinfunction "2_2") (pintype "passive"))
      (node (ref "C27") (pin "2") (pinfunction "2_2") (pintype "passive"))
      (node (ref "C28") (pin "2") (pinfunction "2_2") (pintype "passive"))
      (node (ref "C29") (pin "2") (pinfunction "2_2") (pintype "passive"))
      (node (ref "C30") (pin "2") (pinfunction "2_2") (pintype "passive"))
      (node (ref "C31") (pin "2") (pinfunction "2_2") (pintype "passive"))
      (node (ref "C32") (pin "2") (pinfunction "2_2") (pintype "passive"))
      (node (ref "C33") (pin "2") (pinfunction "2_2") (pintype "passive"))
      (node (ref "C34") (pin "1") (pinfunction "1_1") (pintype "passive"))
      (node (ref "C35") (pin "1") (pinfunction "1_1") (pintype "passive"))
      (node (ref "C36") (pin "1") (pinfunction "1_1") (pintype "passive"))
      (node (ref "C37") (pin "1") (pinfunction "1_1") (pintype "passive"))
      (node (ref "C38") (pin "1") (pinfunction "1_1") (pintype "passive"))
      (node (ref "C39") (pin "1") (pinfunction "1_1") (pintype "passive"))
      (node (ref "C40") (pin "1") (pinfunction "1_1") (pintype "passive"))
      (node (ref "C41") (pin "1") (pinfunction "1_1") (pintype "passive"))
      (node (ref "C42") (pin "1") (pinfunction "1_1") (pintype "passive"))
      (node (ref "C43") (pin "1") (pinfunction "1_1") (pintype "passive"))
      (node (ref "C44") (pin "1") (pinfunction "1_1") (pintype "passive"))
      (node (ref "C45") (pin "1") (pinfunction "1_1") (pintype "passive"))
      (node (ref "C46") (pin "1") (pinfunction "1_1") (pintype "passive"))
      (node (ref "C58") (pin "1") (pinfunction "1_1") (pintype "passive"))
      (node (ref "C59") (pin "1") (pinfunction "1_1") (pintype "passive"))
      (node (ref "C60") (pin "1") (pinfunction "1_1") (pintype "passive"))
      (node (ref "C61") (pin "1") (pinfunction "1_1") (pintype "passive"))
      (node (ref "C62") (pin "1") (pinfunction "1_1") (pintype "passive"))
      (node (ref "C63") (pin "1") (pinfunction "1_1") (pintype "passive"))
      (node (ref "C64") (pin "1") (pinfunction "1_1") (pintype "passive"))
      (node (ref "C65") (pin "1") (pinfunction "1_1") (pintype "passive"))
      (node (ref "C66") (pin "1") (pinfunction "1_1") (pintype "passive"))
      (node (ref "C67") (pin "1") (pinfunction "1_1") (pintype "passive"))
      (node (ref "C69") (pin "1") (pinfunction "1_1") (pintype "passive"))
      (node (ref "C70") (pin "1") (pinfunction "1_1") (pintype "passive"))
      (node (ref "C71") (pin "1") (pinfunction "1_1") (pintype "passive"))
      (node (ref "C72") (pin "1") (pinfunction "1_1") (pintype "passive"))
      (node (ref "C73") (pin "1") (pinfunction "1_1") (pintype "passive"))
      (node (ref "R49") (pin "1") (pinfunction "1_1") (pintype "passive"))
      (node (ref "R51") (pin "1") (pinfunction "1_1") (pintype "passive"))
      (node (ref "R52") (pin "1") (pinfunction "1_1") (pintype "passive"))
      (node (ref "R53") (pin "1") (pinfunction "1_1") (pintype "passive"))
      (node (ref "R54") (pin "1") (pinfunction "1_1") (pintype "passive"))
      (node (ref "R57") (pin "1") (pinfunction "1_1") (pintype "passive"))
      (node (ref "R60") (pin "1") (pinfunction "1_1") (pintype "passive"))
      (node (ref "R61") (pin "1") (pinfunction "1_1") (pintype "passive"))
      (node (ref "R62") (pin "1") (pinfunction "1_1") (pintype "passive"))
      (node (ref "R63") (pin "1") (pinfunction "1_1") (pintype "passive"))
      (node (ref "R64") (pin "1") (pinfunction "1_1") (pintype "passive"))
      (node (ref "R89") (pin "1") (pinfunction "1_1") (pintype "passive"))
      (node (ref "R90") (pin "1") (pinfunction "1_1") (pintype "passive"))
      (node (ref "R91") (pin "2") (pinfunction "2_2") (pintype "passive"))
      (node (ref "R95") (pin "2") (pinfunction "2_2") (pintype "passive"))
      (node (ref "U12") (pin "2") (pinfunction "GND_2") (pintype "power_in"))
      (node (ref "U4") (pin "1") (pinfunction "A0_1") (pintype "input"))
      (node (ref "U4") (pin "2") (pinfunction "A1_2") (pintype "input"))
      (node (ref "U4") (pin "3") (pinfunction "A2_3") (pintype "input"))
      (node (ref "U4") (pin "4") (pinfunction "VSS_4") (pintype "power_in"))
      (node (ref "U4") (pin "7") (pinfunction "WP_7") (pintype "passive"))
      (node (ref "U4") (pin "9") (pinfunction "PAD_9") (pintype "power_in"))
      (node (ref "U5") (pin "33") (pinfunction "GND_33") (pintype "power_in"))
      (node (ref "U6") (pin "33") (pinfunction "GND_33") (pintype "power_in"))
    )
    (net (code "65") (name "Net-(C34-Pad2)") (class "Default")
      (node (ref "C34") (pin "2") (pinfunction "2_2") (pintype "passive"))
      (node (ref "R27") (pin "1") (pinfunction "1_1") (pintype "passive"))
      (node (ref "R28") (pin "1") (pinfunction "1_1") (pintype "passive"))
    )
    (net (code "66") (name "Net-(C35-Pad2)") (class "Default")
      (node (ref "C35") (pin "2") (pinfunction "2_2") (pintype "passive"))
      (node (ref "R29") (pin "1") (pinfunction "1_1") (pintype "passive"))
      (node (ref "R30") (pin "1") (pinfunction "1_1") (pintype "passive"))
    )
    (net (code "67") (name "Net-(D4-Pad1)") (class "Default")
      (node (ref "D4") (pin "1") (pinfunction "1_1") (pintype "passive"))
      (node (ref "R22") (pin "2") (pinfunction "2_2") (pintype "passive"))
    )
    (net (code "68") (name "Net-(D4-Pad2)") (class "Default")
      (node (ref "D4") (pin "2") (pinfunction "2_2") (pintype "passive"))
      (node (ref "R19") (pin "2") (pinfunction "2_2") (pintype "passive"))
    )
    (net (code "69") (name "Net-(D5-Pad1)") (class "Default")
      (node (ref "D5") (pin "1") (pinfunction "1_1") (pintype "passive"))
      (node (ref "R20") (pin "2") (pinfunction "2_2") (pintype "passive"))
    )
    (net (code "70") (name "Net-(D5-Pad2)") (class "Default")
      (node (ref "D5") (pin "2") (pinfunction "2_2") (pintype "passive"))
      (node (ref "R21") (pin "2") (pinfunction "2_2") (pintype "passive"))
    )
    (net (code "71") (name "Net-(D6-Pad1)") (class "Default")
      (node (ref "D6") (pin "1") (pinfunction "1_1") (pintype "passive"))
      (node (ref "R23") (pin "1") (pinfunction "1_1") (pintype "passive"))
    )
    (net (code "72") (name "Net-(D6-Pad2)") (class "Default")
      (node (ref "D6") (pin "2") (pinfunction "2_2") (pintype "passive"))
      (node (ref "R24") (pin "1") (pinfunction "1_1") (pintype "passive"))
    )
    (net (code "73") (name "Net-(R27-Pad2)") (class "Default")
      (node (ref "R27") (pin "2") (pinfunction "2_2") (pintype "passive"))
      (node (ref "TR4") (pin "3") (pinfunction "3_3") (pintype "passive"))
    )
    (net (code "74") (name "Net-(R28-Pad2)") (class "Default")
      (node (ref "R28") (pin "2") (pinfunction "2_2") (pintype "passive"))
      (node (ref "TR3") (pin "3") (pinfunction "3_3") (pintype "passive"))
    )
    (net (code "75") (name "Net-(R29-Pad2)") (class "Default")
      (node (ref "R29") (pin "2") (pinfunction "2_2") (pintype "passive"))
      (node (ref "TR2") (pin "3") (pinfunction "3_3") (pintype "passive"))
    )
    (net (code "76") (name "Net-(R30-Pad2)") (class "Default")
      (node (ref "R30") (pin "2") (pinfunction "2_2") (pintype "passive"))
      (node (ref "TR1") (pin "3") (pinfunction "3_3") (pintype "passive"))
    )
    (net (code "77") (name "Net-(U5-COL{slash}GPIO2)") (class "Default")
      (node (ref "R60") (pin "2") (pinfunction "2_2") (pintype "passive"))
      (node (ref "U5") (pin "29") (pinfunction "COL/GPIO2_29") (pintype "bidirectional"))
    )
    (net (code "78") (name "Net-(U5-CRS{slash}CRS_DV)") (class "Default")
      (node (ref "R58") (pin "1") (pinfunction "1_1") (pintype "passive"))
      (node (ref "U5") (pin "27") (pinfunction "CRS/CRS_DV_27") (pintype "output"))
    )
    (net (code "79") (name "Net-(U5-LED_1{slash}GPIO1)") (class "Default")
      (node (ref "R46") (pin "1") (pinfunction "1_1") (pintype "passive"))
      (node (ref "U5") (pin "24") (pinfunction "LED_1/GPIO1_24") (pintype "bidirectional"))
    )
    (net (code "80") (name "Net-(U5-RBIAS)") (class "Default")
      (node (ref "R95") (pin "1") (pinfunction "1_1") (pintype "passive"))
      (node (ref "U5") (pin "16") (pinfunction "RBIAS_16") (pintype "input"))
    )
    (net (code "81") (name "Net-(U5-~{INT{slash}PWDN})") (class "Default")
      (node (ref "R38") (pin "1") (pinfunction "1_1") (pintype "passive"))
      (node (ref "U5") (pin "8") (pinfunction "~{INT/PWDN}_8") (pintype "output"))
    )
    (net (code "82") (name "Net-(U6-COL{slash}GPIO2)") (class "Default")
      (node (ref "R50") (pin "2") (pinfunction "2_2") (pintype "passive"))
      (node (ref "U6") (pin "29") (pinfunction "COL/GPIO2_29") (pintype "bidirectional"))
    )
    (net (code "83") (name "Net-(U6-CRS{slash}CRS_DV)") (class "Default")
      (node (ref "R55") (pin "1") (pinfunction "1_1") (pintype "passive"))
      (node (ref "U6") (pin "27") (pinfunction "CRS/CRS_DV_27") (pintype "output"))
    )
    (net (code "84") (name "Net-(U6-LED_1{slash}GPIO1)") (class "Default")
      (node (ref "R48") (pin "1") (pinfunction "1_1") (pintype "passive"))
      (node (ref "U6") (pin "24") (pinfunction "LED_1/GPIO1_24") (pintype "bidirectional"))
    )
    (net (code "85") (name "Net-(U6-RBIAS)") (class "Default")
      (node (ref "R91") (pin "1") (pinfunction "1_1") (pintype "passive"))
      (node (ref "U6") (pin "16") (pinfunction "RBIAS_16") (pintype "input"))
    )
    (net (code "86") (name "Net-(U6-~{INT{slash}PWDN})") (class "Default")
      (node (ref "R37") (pin "1") (pinfunction "1_1") (pintype "passive"))
      (node (ref "U6") (pin "8") (pinfunction "~{INT/PWDN}_8") (pintype "output"))
    )
    (net (code "87") (name "Net-(U12-1Y)") (class "Default")
      (node (ref "D6") (pin "4") (pinfunction "4_4") (pintype "passive"))
      (node (ref "U12") (pin "6") (pinfunction "1Y_6") (pintype "output"))
    )
    (net (code "88") (name "Net-(U12-2Y)") (class "Default")
      (node (ref "D6") (pin "3") (pinfunction "3_3") (pintype "passive"))
      (node (ref "U12") (pin "4") (pinfunction "2Y_4") (pintype "output"))
    )
    (net (code "89") (name "VDD_3V3") (class "Default")
      (node (ref "C26") (pin "1") (pinfunction "1_1") (pintype "passive"))
      (node (ref "C27") (pin "1") (pinfunction "1_1") (pintype "passive"))
      (node (ref "C28") (pin "1") (pinfunction "1_1") (pintype "passive"))
      (node (ref "C29") (pin "1") (pinfunction "1_1") (pintype "passive"))
      (node (ref "C30") (pin "1") (pinfunction "1_1") (pintype "passive"))
      (node (ref "C31") (pin "1") (pinfunction "1_1") (pintype "passive"))
      (node (ref "C32") (pin "1") (pinfunction "1_1") (pintype "passive"))
      (node (ref "C33") (pin "1") (pinfunction "1_1") (pintype "passive"))
      (node (ref "C36") (pin "2") (pinfunction "2_2") (pintype "passive"))
      (node (ref "C37") (pin "2") (pinfunction "2_2") (pintype "passive"))
      (node (ref "C38") (pin "2") (pinfunction "2_2") (pintype "passive"))
      (node (ref "C39") (pin "2") (pinfunction "2_2") (pintype "passive"))
      (node (ref "C40") (pin "2") (pinfunction "2_2") (pintype "passive"))
      (node (ref "C41") (pin "2") (pinfunction "2_2") (pintype "passive"))
      (node (ref "C42") (pin "2") (pinfunction "2_2") (pintype "passive"))
      (node (ref "C43") (pin "2") (pinfunction "2_2") (pintype "passive"))
      (node (ref "C44") (pin "2") (pinfunction "2_2") (pintype "passive"))
      (node (ref "C45") (pin "2") (pinfunction "2_2") (pintype "passive"))
      (node (ref "C46") (pin "2") (pinfunction "2_2") (pintype "passive"))
      (node (ref "C58") (pin "2") (pinfunction "2_2") (pintype "passive"))
      (node (ref "C59") (pin "2") (pinfunction "2_2") (pintype "passive"))
      (node (ref "C60") (pin "2") (pinfunction "2_2") (pintype "passive"))
      (node (ref "C61") (pin "2") (pinfunction "2_2") (pintype "passive"))
      (node (ref "C62") (pin "2") (pinfunction "2_2") (pintype "passive"))
      (node (ref "C63") (pin "2") (pinfunction "2_2") (pintype "passive"))
      (node (ref "C64") (pin "2") (pinfunction "2_2") (pintype "passive"))
      (node (ref "C65") (pin "2") (pinfunction "2_2") (pintype "passive"))
      (node (ref "C66") (pin "2") (pinfunction "2_2") (pintype "passive"))
      (node (ref "C67") (pin "2") (pinfunction "2_2") (pintype "passive"))
      (node (ref "C69") (pin "2") (pinfunction "2_2") (pintype "passive"))
      (node (ref "C70") (pin "2") (pinfunction "2_2") (pintype "passive"))
      (node (ref "C71") (pin "2") (pinfunction "2_2") (pintype "passive"))
      (node (ref "C72") (pin "2") (pinfunction "2_2") (pintype "passive"))
      (node (ref "C73") (pin "2") (pinfunction "2_2") (pintype "passive"))
      (node (ref "R19") (pin "1") (pinfunction "1_1") (pintype "passive"))
      (node (ref "R20") (pin "1") (pinfunction "1_1") (pintype "passive"))
      (node (ref "R21") (pin "1") (pinfunction "1_1") (pintype "passive"))
      (node (ref "R22") (pin "1") (pinfunction "1_1") (pintype "passive"))
      (node (ref "R23") (pin "2") (pinfunction "2_2") (pintype "passive"))
      (node (ref "R24") (pin "2") (pinfunction "2_2") (pintype "passive"))
      (node (ref "R31") (pin "1") (pinfunction "1_1") (pintype "passive"))
      (node (ref "R32") (pin "1") (pinfunction "1_1") (pintype "passive"))
      (node (ref "R33") (pin "1") (pinfunction "1_1") (pintype "passive"))
      (node (ref "R34") (pin "1") (pinfunction "1_1") (pintype "passive"))
      (node (ref "R35") (pin "2") (pinfunction "2_2") (pintype "passive"))
      (node (ref "R36") (pin "2") (pinfunction "2_2") (pintype "passive"))
      (node (ref "R37") (pin "2") (pinfunction "2_2") (pintype "passive"))
      (node (ref "R38") (pin "2") (pinfunction "2_2") (pintype "passive"))
      (node (ref "R39") (pin "2") (pinfunction "2_2") (pintype "passive"))
      (node (ref "R40") (pin "2") (pinfunction "2_2") (pintype "passive"))
      (node (ref "R41") (pin "2") (pinfunction "2_2") (pintype "passive"))
      (node (ref "R42") (pin "2") (pinfunction "2_2") (pintype "passive"))
      (node (ref "R46") (pin "2") (pinfunction "2_2") (pintype "passive"))
      (node (ref "R48") (pin "2") (pinfunction "2_2") (pintype "passive"))
      (node (ref "R50") (pin "1") (pinfunction "1_1") (pintype "passive"))
      (node (ref "R55") (pin "2") (pinfunction "2_2") (pintype "passive"))
      (node (ref "R56") (pin "2") (pinfunction "2_2") (pintype "passive"))
      (node (ref "R58") (pin "2") (pinfunction "2_2") (pintype "passive"))
      (node (ref "R59") (pin "2") (pinfunction "2_2") (pintype "passive"))
      (node (ref "R92") (pin "1") (pinfunction "1_1") (pintype "passive"))
      (node (ref "R93") (pin "1") (pinfunction "1_1") (pintype "passive"))
      (node (ref "R94") (pin "1") (pinfunction "1_1") (pintype "passive"))
      (node (ref "R96") (pin "1") (pinfunction "1_1") (pintype "passive"))
      (node (ref "TR1") (pin "6") (pinfunction "6_6") (pintype "passive"))
      (node (ref "TR2") (pin "6") (pinfunction "6_6") (pintype "passive"))
      (node (ref "TR3") (pin "6") (pinfunction "6_6") (pintype "passive"))
      (node (ref "TR4") (pin "6") (pinfunction "6_6") (pintype "passive"))
      (node (ref "U12") (pin "5") (pinfunction "VCC_5") (pintype "power_in"))
      (node (ref "U4") (pin "8") (pinfunction "VCC_8") (pintype "power_in"))
      (node (ref "U5") (pin "14") (pinfunction "AVD_14") (pintype "power_in"))
      (node (ref "U5") (pin "21") (pinfunction "VDDIO_21") (pintype "power_in"))
      (node (ref "U6") (pin "14") (pinfunction "AVD_14") (pintype "power_in"))
      (node (ref "U6") (pin "21") (pinfunction "VDDIO_21") (pintype "power_in"))
    )
    (net (code "90") (name "unconnected-(U5-NC-Pad13)") (class "Default")
      (node (ref "U5") (pin "13") (pinfunction "NC_13") (pintype "passive"))
    )
    (net (code "91") (name "unconnected-(U5-NC-Pad15)") (class "Default")
      (node (ref "U5") (pin "15") (pinfunction "NC_15") (pintype "passive"))
    )
    (net (code "92") (name "unconnected-(U5-XO-Pad22)") (class "Default")
      (node (ref "U5") (pin "22") (pinfunction "XO_22") (pintype "output"))
    )
    (net (code "93") (name "unconnected-(U6-NC-Pad13)") (class "Default")
      (node (ref "U6") (pin "13") (pinfunction "NC_13") (pintype "passive"))
    )
    (net (code "94") (name "unconnected-(U6-NC-Pad15)") (class "Default")
      (node (ref "U6") (pin "15") (pinfunction "NC_15") (pintype "passive"))
    )
    (net (code "95") (name "unconnected-(U6-XO-Pad22)") (class "Default")
      (node (ref "U6") (pin "22") (pinfunction "XO_22") (pintype "output"))
    )
  )
)
